# PowerSupply.net
KiCad netlist of a schematic drawn in Altium Designer
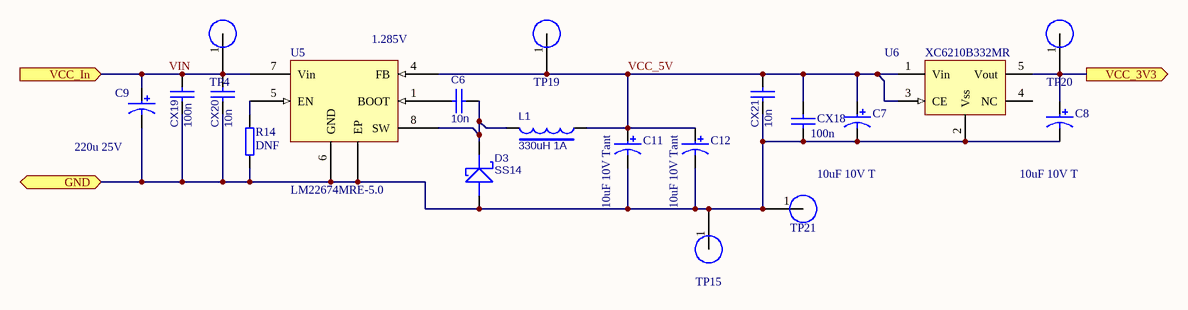
[diagram p0: PowerSupply.SchDoc]

(export (version "E")
  (design (tool "Eeschema 10.0.6"))
  (components
    (comp (ref "C6") (value "10n") (footprint "0603") (libsource (lib "*") (part "CAP")))
    (comp (ref "C7")
      (value "10uF 10V T")
      (footprint "SMD-TANT-A")
      (libsource (lib "DEVICE") (part "CAPACITOR POL-S"))
    )
    (comp (ref "C8")
      (value "10uF 10V T")
      (footprint "SMD-TANT-A")
      (libsource (lib "DEVICE") (part "CAPACITOR POL-S"))
    )
    (comp (ref "C9")
      (value "220u 25V")
      (footprint "RB.15/.32")
      (libsource (lib "DEVICE") (part "CAPACITOR POL-S"))
    )
    (comp (ref "C11")
      (value "10uF 10V Tant")
      (footprint "SMD-TANT-A")
      (libsource (lib "DEVICE") (part "CAPACITOR POL-S"))
    )
    (comp (ref "C12")
      (value "10uF 10V Tant")
      (footprint "SMD-TANT-A")
      (libsource (lib "DEVICE") (part "CAPACITOR POL-S"))
    )
    (comp (ref "CX18") (value "100n") (footprint "0603") (libsource (lib "DEVICE") (part "CAP")))
    (comp (ref "CX19") (value "100n") (footprint "0603") (libsource (lib "*") (part "CAP")))
    (comp (ref "CX20") (value "10n") (footprint "0603") (libsource (lib "*") (part "CAP")))
    (comp (ref "CX21") (value "10n") (footprint "0603") (libsource (lib "*") (part "CAP")))
    (comp (ref "D3") (value "SS14") (footprint "DO-214AC") (libsource (lib "DEVICE") (part "DIODE SCHOTTKY")))
    (comp (ref "L1") (value "330uH 1A") (footprint "INDUCTOR16") (libsource (lib "*") (part "INDUCTOR2")))
    (comp (ref "R14") (value "DNF") (footprint "0603") (libsource (lib "DEVICE") (part "RES8")))
    (comp (ref "TP4")
      (value "TestPad")
      (footprint "TestPad")
      (description "Test Pad")
      (libsource (lib "Hardware") (part "TestPad"))
    )
    (comp (ref "TP15")
      (value "TestPad")
      (footprint "TestPad")
      (description "Test Pad")
      (libsource (lib "Hardware") (part "TestPad"))
    )
    (comp (ref "TP19")
      (value "TestPad")
      (footprint "TestPad")
      (description "Test Pad")
      (libsource (lib "Hardware") (part "TestPad"))
    )
    (comp (ref "TP20")
      (value "TestPad")
      (footprint "TestPad")
      (description "Test Pad")
      (libsource (lib "Hardware") (part "TestPad"))
    )
    (comp (ref "TP21")
      (value "TestPad")
      (footprint "TestPad")
      (description "Test Pad")
      (libsource (lib "Hardware") (part "TestPad"))
    )
    (comp (ref "U5")
      (value "LM22674MRE-5.0")
      (footprint "PSOP-8")
      (description "0.5A SMPS, Fixed - 5V")
      (libsource (lib "NS-EXTRA") (part "LM22675"))
    )
    (comp (ref "U6")
      (value "XC6210B332MR")
      (footprint "SOT-25-A")
      (description "3.3 LDO")
      (libsource (lib "Torex") (part "XC6204B"))
    )
  )
  (nets
    (net (code "1") (name "/GND") (class "Default")
      (node (ref "C11") (pin "2") (pinfunction "2_2") (pintype "passive"))
      (node (ref "C12") (pin "2") (pinfunction "2_2") (pintype "passive"))
      (node (ref "C7") (pin "2") (pinfunction "2_2") (pintype "passive"))
      (node (ref "C8") (pin "2") (pinfunction "2_2") (pintype "passive"))
      (node (ref "C9") (pin "2") (pinfunction "2_2") (pintype "passive"))
      (node (ref "CX18") (pin "2") (pintype "passive"))
      (node (ref "CX19") (pin "1") (pintype "passive"))
      (node (ref "CX20") (pin "1") (pintype "passive"))
      (node (ref "CX21") (pin "1") (pintype "passive"))
      (node (ref "D3") (pin "A") (pinfunction "A_A") (pintype "passive"))
      (node (ref "R14") (pin "1") (pintype "passive"))
      (node (ref "TP15") (pin "1") (pintype "passive"))
      (node (ref "TP21") (pin "1") (pintype "passive"))
      (node (ref "U5") (pin "6") (pinfunction "GND_6") (pintype "power_in"))
      (node (ref "U5") (pin "9") (pinfunction "EP_9") (pintype "power_in"))
      (node (ref "U6") (pin "2") (pinfunction "Vss_2") (pintype "power_in"))
    )
    (net (code "2") (name "/VCC_3V3") (class "Default")
      (node (ref "C8") (pin "1") (pinfunction "1_1") (pintype "passive"))
      (node (ref "TP20") (pin "1") (pintype "passive"))
      (node (ref "U6") (pin "5") (pinfunction "Vout_5") (pintype "power_in"))
    )
    (net (code "3") (name "/VCC_5V") (class "Default")
      (node (ref "C11") (pin "1") (pinfunction "1_1") (pintype "passive"))
      (node (ref "C12") (pin "1") (pinfunction "1_1") (pintype "passive"))
      (node (ref "C7") (pin "1") (pinfunction "1_1") (pintype "passive"))
      (node (ref "CX18") (pin "1") (pintype "passive"))
      (node (ref "CX21") (pin "2") (pintype "passive"))
      (node (ref "L1") (pin "2") (pintype "passive"))
      (node (ref "TP19") (pin "1") (pintype "passive"))
      (node (ref "U5") (pin "4") (pinfunction "FB_4") (pintype "input"))
      (node (ref "U6") (pin "1") (pinfunction "Vin_1") (pintype "power_in"))
      (node (ref "U6") (pin "3") (pinfunction "CE_3") (pintype "input"))
    )
    (net (code "4") (name "/VIN") (class "Default")
      (node (ref "C9") (pin "1") (pinfunction "1_1") (pintype "passive"))
      (node (ref "CX19") (pin "2") (pintype "passive"))
      (node (ref "CX20") (pin "2") (pintype "passive"))
      (node (ref "TP4") (pin "1") (pintype "passive"))
      (node (ref "U5") (pin "7") (pinfunction "Vin_7") (pintype "passive"))
    )
    (net (code "5") (name "Net-(U5-BOOT)") (class "Default")
      (node (ref "C6") (pin "1") (pintype "passive"))
      (node (ref "U5") (pin "1") (pinfunction "BOOT_1") (pintype "input"))
    )
    (net (code "6") (name "Net-(U5-EN)") (class "Default")
      (node (ref "R14") (pin "2") (pintype "passive"))
      (node (ref "U5") (pin "5") (pinfunction "EN_5") (pintype "input"))
    )
    (net (code "7") (name "Net-(U5-SW)") (class "Default")
      (node (ref "C6") (pin "2") (pintype "passive"))
      (node (ref "D3") (pin "K") (pinfunction "K_K") (pintype "passive"))
      (node (ref "L1") (pin "1") (pintype "passive"))
      (node (ref "U5") (pin "8") (pinfunction "SW_8") (pintype "power_in"))
    )
    (net (code "8") (name "unconnected-(U6-NC-Pad4)") (class "Default")
      (node (ref "U6") (pin "4") (pinfunction "NC_4") (pintype "passive"))
    )
  )
)
